# SolarSynth.net
KiCad netlist of a schematic drawn in EAGLE
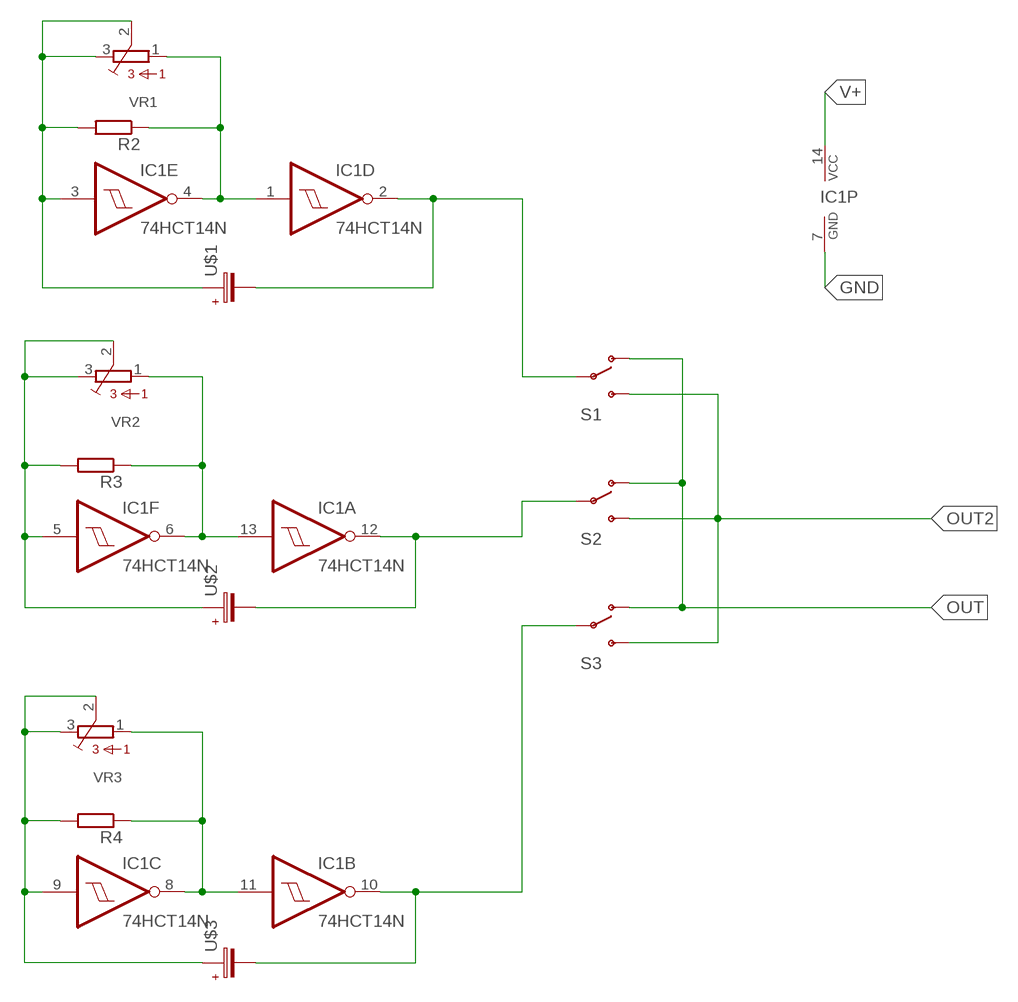
[diagram p0: schematic, sheet 1]

(export (version "E")
  (design (tool "Eeschema 10.0.6"))
  (components
    (comp (ref "IC1")
      (value "74HCT14N")
      (footprint "eagle-import:DIL14")
      (libsource (lib "eagle-import") (part "7414NHCT"))
    )
    (comp (ref "R2")
      (value "R-EU_0207/7")
      (footprint "eagle-import:0207_7")
      (libsource (lib "eagle-import") (part "R-EU_0207/7"))
    )
    (comp (ref "R3")
      (value "R-EU_0207/7")
      (footprint "eagle-import:0207_7")
      (libsource (lib "eagle-import") (part "R-EU_0207/7"))
    )
    (comp (ref "R4")
      (value "R-EU_0207/7")
      (footprint "eagle-import:0207_7")
      (libsource (lib "eagle-import") (part "R-EU_0207/7"))
    )
    (comp (ref "S1")
      (value "SWITCH-SPDTKIT")
      (footprint "eagle-import:SWITCH-SPDT_KIT")
      (libsource (lib "eagle-import") (part "SWITCH-SPDTKIT"))
    )
    (comp (ref "S2")
      (value "SWITCH-SPDTKIT")
      (footprint "eagle-import:SWITCH-SPDT_KIT")
      (libsource (lib "eagle-import") (part "SWITCH-SPDTKIT"))
    )
    (comp (ref "S3")
      (value "SWITCH-SPDTKIT")
      (footprint "eagle-import:SWITCH-SPDT_KIT")
      (libsource (lib "eagle-import") (part "SWITCH-SPDTKIT"))
    )
    (comp (ref "U$1")
      (value "080-EU")
      (footprint "eagle-import:080_025")
      (libsource (lib "eagle-import") (part "080-EU"))
    )
    (comp (ref "U$2")
      (value "080-EU")
      (footprint "eagle-import:080_025")
      (libsource (lib "eagle-import") (part "080-EU"))
    )
    (comp (ref "U$3")
      (value "080-EU")
      (footprint "eagle-import:080_025")
      (libsource (lib "eagle-import") (part "080-EU"))
    )
    (comp (ref "VR1")
      (value "BOURNS_3362P_TRIMMERP")
      (footprint "eagle-import:BOURNS_3362P_TRIMMER")
      (libsource (lib "eagle-import") (part "BOURNS_3362P_TRIMMERP"))
    )
    (comp (ref "VR2")
      (value "BOURNS_3362P_TRIMMERP")
      (footprint "eagle-import:BOURNS_3362P_TRIMMER")
      (libsource (lib "eagle-import") (part "BOURNS_3362P_TRIMMERP"))
    )
    (comp (ref "VR3")
      (value "BOURNS_3362P_TRIMMERP")
      (footprint "eagle-import:BOURNS_3362P_TRIMMER")
      (libsource (lib "eagle-import") (part "BOURNS_3362P_TRIMMERP"))
    )
  )
  (nets
    (net (code "1") (name "GND") (class "Default")
      (node (ref "IC1") (pin "7") (pinfunction "GND_7") (pintype "power_in"))
    )
    (net (code "2") (name "Net-(IC1A-I)") (class "Default")
      (node (ref "IC1") (pin "13") (pinfunction "I_13") (pintype "input"))
      (node (ref "IC1") (pin "6") (pinfunction "O_6") (pintype "output"))
      (node (ref "R3") (pin "1") (pinfunction "1_1") (pintype "passive"))
      (node (ref "VR2") (pin "1") (pinfunction "1_1") (pintype "passive"))
    )
    (net (code "3") (name "Net-(IC1A-O)") (class "Default")
      (node (ref "IC1") (pin "12") (pinfunction "O_12") (pintype "output"))
      (node (ref "S2") (pin "2") (pinfunction "P_2") (pintype "passive"))
      (node (ref "U$2") (pin "-") (pinfunction "-_-") (pintype "passive"))
    )
    (net (code "4") (name "Net-(IC1B-I)") (class "Default")
      (node (ref "IC1") (pin "11") (pinfunction "I_11") (pintype "input"))
      (node (ref "IC1") (pin "8") (pinfunction "O_8") (pintype "output"))
      (node (ref "R4") (pin "1") (pinfunction "1_1") (pintype "passive"))
      (node (ref "VR3") (pin "1") (pinfunction "1_1") (pintype "passive"))
    )
    (net (code "5") (name "Net-(IC1B-O)") (class "Default")
      (node (ref "IC1") (pin "10") (pinfunction "O_10") (pintype "output"))
      (node (ref "S3") (pin "2") (pinfunction "P_2") (pintype "passive"))
      (node (ref "U$3") (pin "-") (pinfunction "-_-") (pintype "passive"))
    )
    (net (code "6") (name "Net-(IC1C-I)") (class "Default")
      (node (ref "IC1") (pin "9") (pinfunction "I_9") (pintype "input"))
      (node (ref "R4") (pin "2") (pinfunction "2_2") (pintype "passive"))
      (node (ref "U$3") (pin "+") (pinfunction "+_+") (pintype "passive"))
      (node (ref "VR3") (pin "2") (pinfunction "2_2") (pintype "passive"))
      (node (ref "VR3") (pin "3") (pinfunction "3_3") (pintype "passive"))
    )
    (net (code "7") (name "Net-(IC1D-I)") (class "Default")
      (node (ref "IC1") (pin "1") (pinfunction "I_1") (pintype "input"))
      (node (ref "IC1") (pin "4") (pinfunction "O_4") (pintype "output"))
      (node (ref "R2") (pin "1") (pinfunction "1_1") (pintype "passive"))
      (node (ref "VR1") (pin "1") (pinfunction "1_1") (pintype "passive"))
    )
    (net (code "8") (name "Net-(IC1D-O)") (class "Default")
      (node (ref "IC1") (pin "2") (pinfunction "O_2") (pintype "output"))
      (node (ref "S1") (pin "2") (pinfunction "P_2") (pintype "passive"))
      (node (ref "U$1") (pin "-") (pinfunction "-_-") (pintype "passive"))
    )
    (net (code "9") (name "Net-(IC1E-I)") (class "Default")
      (node (ref "IC1") (pin "3") (pinfunction "I_3") (pintype "input"))
      (node (ref "R2") (pin "2") (pinfunction "2_2") (pintype "passive"))
      (node (ref "U$1") (pin "+") (pinfunction "+_+") (pintype "passive"))
      (node (ref "VR1") (pin "2") (pinfunction "2_2") (pintype "passive"))
      (node (ref "VR1") (pin "3") (pinfunction "3_3") (pintype "passive"))
    )
    (net (code "10") (name "Net-(IC1F-I)") (class "Default")
      (node (ref "IC1") (pin "5") (pinfunction "I_5") (pintype "input"))
      (node (ref "R3") (pin "2") (pinfunction "2_2") (pintype "passive"))
      (node (ref "U$2") (pin "+") (pinfunction "+_+") (pintype "passive"))
      (node (ref "VR2") (pin "2") (pinfunction "2_2") (pintype "passive"))
      (node (ref "VR2") (pin "3") (pinfunction "3_3") (pintype "passive"))
    )
    (net (code "11") (name "OUT") (class "Default")
      (node (ref "S1") (pin "1") (pinfunction "O_1") (pintype "passive"))
      (node (ref "S2") (pin "1") (pinfunction "O_1") (pintype "passive"))
      (node (ref "S3") (pin "1") (pinfunction "O_1") (pintype "passive"))
    )
    (net (code "12") (name "OUT2") (class "Default")
      (node (ref "S1") (pin "3") (pinfunction "S_3") (pintype "passive"))
      (node (ref "S2") (pin "3") (pinfunction "S_3") (pintype "passive"))
      (node (ref "S3") (pin "3") (pinfunction "S_3") (pintype "passive"))
    )
    (net (code "13") (name "V+") (class "Default")
      (node (ref "IC1") (pin "14") (pinfunction "VCC_14") (pintype "power_in"))
    )
  )
)
